# FlexiGlow_Rev_A.net
KiCad netlist of a schematic drawn in Altium Designer
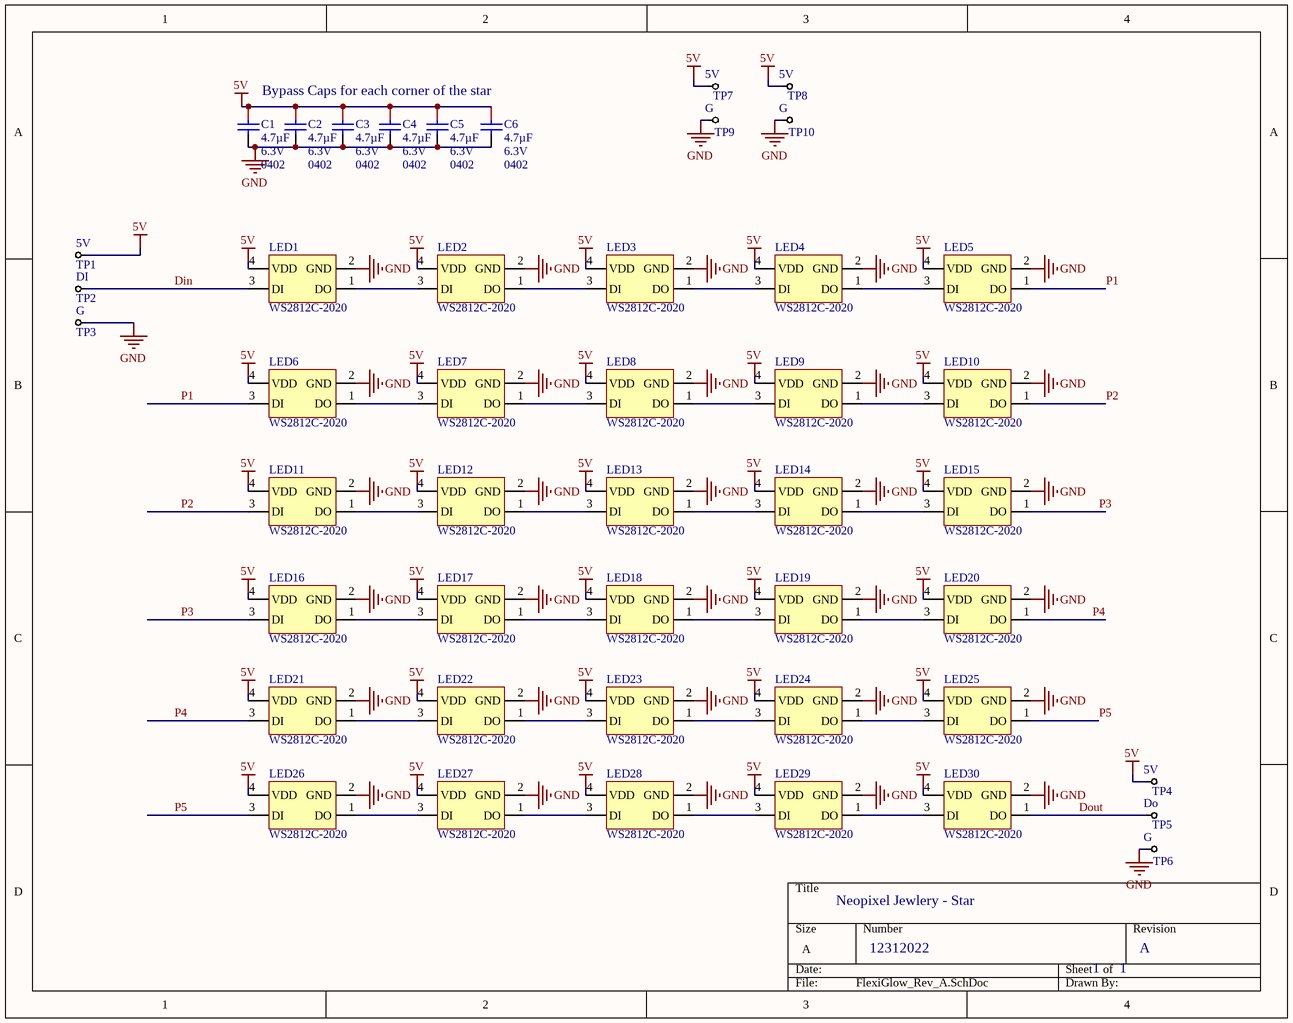
[diagram p0: FlexiGlow_Rev_A.SchDoc]

(export (version "E")
  (design (tool "Eeschema 10.0.6"))
  (components
    (comp (ref "C1")
      (value "4.7uF")
      (footprint "CAPC0402(1005)_N")
      (description "4.7uF 0402")
      (fields
        (field (name "MANUFACTURER") "Murata Electronics North America")
        (field (name "MANUFACTURER PART NUMBER") "GRM155R60J475ME47D")
        (field (name "CAPACITANCE") "4.7µF")
        (field (name "VOLTAGE - RATED") "6.3V")
        (field (name "PACKAGE / CASE") "0402")
      )
      (libsource (lib "Kyle-Passive") (part "CAP CER 4.7UF 6.3V 10% X5R 0402"))
    )
    (comp (ref "C2")
      (value "4.7uF")
      (footprint "CAPC0402(1005)_N")
      (description "4.7uF 0402")
      (fields
        (field (name "MANUFACTURER") "Murata Electronics North America")
        (field (name "MANUFACTURER PART NUMBER") "GRM155R60J475ME47D")
        (field (name "CAPACITANCE") "4.7µF")
        (field (name "VOLTAGE - RATED") "6.3V")
        (field (name "PACKAGE / CASE") "0402")
      )
      (libsource (lib "Kyle-Passive") (part "CAP CER 4.7UF 6.3V 10% X5R 0402"))
    )
    (comp (ref "C3")
      (value "4.7uF")
      (footprint "CAPC0402(1005)_N")
      (description "4.7uF 0402")
      (fields
        (field (name "MANUFACTURER") "Murata Electronics North America")
        (field (name "MANUFACTURER PART NUMBER") "GRM155R60J475ME47D")
        (field (name "CAPACITANCE") "4.7µF")
        (field (name "VOLTAGE - RATED") "6.3V")
        (field (name "PACKAGE / CASE") "0402")
      )
      (libsource (lib "Kyle-Passive") (part "CAP CER 4.7UF 6.3V 10% X5R 0402"))
    )
    (comp (ref "C4")
      (value "4.7uF")
      (footprint "CAPC0402(1005)_N")
      (description "4.7uF 0402")
      (fields
        (field (name "MANUFACTURER") "Murata Electronics North America")
        (field (name "MANUFACTURER PART NUMBER") "GRM155R60J475ME47D")
        (field (name "CAPACITANCE") "4.7µF")
        (field (name "VOLTAGE - RATED") "6.3V")
        (field (name "PACKAGE / CASE") "0402")
      )
      (libsource (lib "Kyle-Passive") (part "CAP CER 4.7UF 6.3V 10% X5R 0402"))
    )
    (comp (ref "C5")
      (value "4.7uF")
      (footprint "CAPC0402(1005)_N")
      (description "4.7uF 0402")
      (fields
        (field (name "MANUFACTURER") "Murata Electronics North America")
        (field (name "MANUFACTURER PART NUMBER") "GRM155R60J475ME47D")
        (field (name "CAPACITANCE") "4.7µF")
        (field (name "VOLTAGE - RATED") "6.3V")
        (field (name "PACKAGE / CASE") "0402")
      )
      (libsource (lib "Kyle-Passive") (part "CAP CER 4.7UF 6.3V 10% X5R 0402"))
    )
    (comp (ref "C6")
      (value "4.7uF")
      (footprint "CAPC0402(1005)_N")
      (description "4.7uF 0402")
      (fields
        (field (name "MANUFACTURER") "Murata Electronics North America")
        (field (name "MANUFACTURER PART NUMBER") "GRM155R60J475ME47D")
        (field (name "CAPACITANCE") "4.7µF")
        (field (name "VOLTAGE - RATED") "6.3V")
        (field (name "PACKAGE / CASE") "0402")
      )
      (libsource (lib "Kyle-Passive") (part "CAP CER 4.7UF 6.3V 10% X5R 0402"))
    )
    (comp (ref "LED1")
      (value "WS2812C-2020")
      (footprint "WS2812C-2020")
      (description "Neopixel")
      (libsource (lib "Kyle-Diode-Opto-LED") (part "WS2812C-2020"))
    )
    (comp (ref "LED2")
      (value "WS2812C-2020")
      (footprint "WS2812C-2020")
      (description "Neopixel")
      (libsource (lib "Kyle-Diode-Opto-LED") (part "WS2812C-2020"))
    )
    (comp (ref "LED3")
      (value "WS2812C-2020")
      (footprint "WS2812C-2020")
      (description "Neopixel")
      (libsource (lib "Kyle-Diode-Opto-LED") (part "WS2812C-2020"))
    )
    (comp (ref "LED4")
      (value "WS2812C-2020")
      (footprint "WS2812C-2020")
      (description "Neopixel")
      (libsource (lib "Kyle-Diode-Opto-LED") (part "WS2812C-2020"))
    )
    (comp (ref "LED5")
      (value "WS2812C-2020")
      (footprint "WS2812C-2020")
      (description "Neopixel")
      (libsource (lib "Kyle-Diode-Opto-LED") (part "WS2812C-2020"))
    )
    (comp (ref "LED6")
      (value "WS2812C-2020")
      (footprint "WS2812C-2020")
      (description "Neopixel")
      (libsource (lib "Kyle-Diode-Opto-LED") (part "WS2812C-2020"))
    )
    (comp (ref "LED7")
      (value "WS2812C-2020")
      (footprint "WS2812C-2020")
      (description "Neopixel")
      (libsource (lib "Kyle-Diode-Opto-LED") (part "WS2812C-2020"))
    )
    (comp (ref "LED8")
      (value "WS2812C-2020")
      (footprint "WS2812C-2020")
      (description "Neopixel")
      (libsource (lib "Kyle-Diode-Opto-LED") (part "WS2812C-2020"))
    )
    (comp (ref "LED9")
      (value "WS2812C-2020")
      (footprint "WS2812C-2020")
      (description "Neopixel")
      (libsource (lib "Kyle-Diode-Opto-LED") (part "WS2812C-2020"))
    )
    (comp (ref "LED10")
      (value "WS2812C-2020")
      (footprint "WS2812C-2020")
      (description "Neopixel")
      (libsource (lib "Kyle-Diode-Opto-LED") (part "WS2812C-2020"))
    )
    (comp (ref "LED11")
      (value "WS2812C-2020")
      (footprint "WS2812C-2020")
      (description "Neopixel")
      (libsource (lib "Kyle-Diode-Opto-LED") (part "WS2812C-2020"))
    )
    (comp (ref "LED12")
      (value "WS2812C-2020")
      (footprint "WS2812C-2020")
      (description "Neopixel")
      (libsource (lib "Kyle-Diode-Opto-LED") (part "WS2812C-2020"))
    )
    (comp (ref "LED13")
      (value "WS2812C-2020")
      (footprint "WS2812C-2020")
      (description "Neopixel")
      (libsource (lib "Kyle-Diode-Opto-LED") (part "WS2812C-2020"))
    )
    (comp (ref "LED14")
      (value "WS2812C-2020")
      (footprint "WS2812C-2020")
      (description "Neopixel")
      (libsource (lib "Kyle-Diode-Opto-LED") (part "WS2812C-2020"))
    )
    (comp (ref "LED15")
      (value "WS2812C-2020")
      (footprint "WS2812C-2020")
      (description "Neopixel")
      (libsource (lib "Kyle-Diode-Opto-LED") (part "WS2812C-2020"))
    )
    (comp (ref "LED16")
      (value "WS2812C-2020")
      (footprint "WS2812C-2020")
      (description "Neopixel")
      (libsource (lib "Kyle-Diode-Opto-LED") (part "WS2812C-2020"))
    )
    (comp (ref "LED17")
      (value "WS2812C-2020")
      (footprint "WS2812C-2020")
      (description "Neopixel")
      (libsource (lib "Kyle-Diode-Opto-LED") (part "WS2812C-2020"))
    )
    (comp (ref "LED18")
      (value "WS2812C-2020")
      (footprint "WS2812C-2020")
      (description "Neopixel")
      (libsource (lib "Kyle-Diode-Opto-LED") (part "WS2812C-2020"))
    )
    (comp (ref "LED19")
      (value "WS2812C-2020")
      (footprint "WS2812C-2020")
      (description "Neopixel")
      (libsource (lib "Kyle-Diode-Opto-LED") (part "WS2812C-2020"))
    )
    (comp (ref "LED20")
      (value "WS2812C-2020")
      (footprint "WS2812C-2020")
      (description "Neopixel")
      (libsource (lib "Kyle-Diode-Opto-LED") (part "WS2812C-2020"))
    )
    (comp (ref "LED21")
      (value "WS2812C-2020")
      (footprint "WS2812C-2020")
      (description "Neopixel")
      (libsource (lib "Kyle-Diode-Opto-LED") (part "WS2812C-2020"))
    )
    (comp (ref "LED22")
      (value "WS2812C-2020")
      (footprint "WS2812C-2020")
      (description "Neopixel")
      (libsource (lib "Kyle-Diode-Opto-LED") (part "WS2812C-2020"))
    )
    (comp (ref "LED23")
      (value "WS2812C-2020")
      (footprint "WS2812C-2020")
      (description "Neopixel")
      (libsource (lib "Kyle-Diode-Opto-LED") (part "WS2812C-2020"))
    )
    (comp (ref "LED24")
      (value "WS2812C-2020")
      (footprint "WS2812C-2020")
      (description "Neopixel")
      (libsource (lib "Kyle-Diode-Opto-LED") (part "WS2812C-2020"))
    )
    (comp (ref "LED25")
      (value "WS2812C-2020")
      (footprint "WS2812C-2020")
      (description "Neopixel")
      (libsource (lib "Kyle-Diode-Opto-LED") (part "WS2812C-2020"))
    )
    (comp (ref "LED26")
      (value "WS2812C-2020")
      (footprint "WS2812C-2020")
      (description "Neopixel")
      (libsource (lib "Kyle-Diode-Opto-LED") (part "WS2812C-2020"))
    )
    (comp (ref "LED27")
      (value "WS2812C-2020")
      (footprint "WS2812C-2020")
      (description "Neopixel")
      (libsource (lib "Kyle-Diode-Opto-LED") (part "WS2812C-2020"))
    )
    (comp (ref "LED28")
      (value "WS2812C-2020")
      (footprint "WS2812C-2020")
      (description "Neopixel")
      (libsource (lib "Kyle-Diode-Opto-LED") (part "WS2812C-2020"))
    )
    (comp (ref "LED29")
      (value "WS2812C-2020")
      (footprint "WS2812C-2020")
      (description "Neopixel")
      (libsource (lib "Kyle-Diode-Opto-LED") (part "WS2812C-2020"))
    )
    (comp (ref "LED30")
      (value "WS2812C-2020")
      (footprint "WS2812C-2020")
      (description "Neopixel")
      (libsource (lib "Kyle-Diode-Opto-LED") (part "WS2812C-2020"))
    )
    (comp (ref "TP1")
      (value "5V")
      (footprint "TestPoint-Micro")
      (description "Test Point")
      (libsource (lib "Kyle-Misc") (part "TestPoint, small"))
    )
    (comp (ref "TP2")
      (value "DI")
      (footprint "TestPoint-Micro")
      (description "Test Point")
      (libsource (lib "Kyle-Misc") (part "TestPoint, small"))
    )
    (comp (ref "TP3")
      (value "G")
      (footprint "TestPoint-Micro")
      (description "Test Point")
      (libsource (lib "Kyle-Misc") (part "TestPoint, small"))
    )
    (comp (ref "TP4")
      (value "5V")
      (footprint "TestPoint-Micro")
      (description "Test Point")
      (libsource (lib "Kyle-Misc") (part "TestPoint, small"))
    )
    (comp (ref "TP5")
      (value "Do")
      (footprint "TestPoint-Micro")
      (description "Test Point")
      (libsource (lib "Kyle-Misc") (part "TestPoint, small"))
    )
    (comp (ref "TP6")
      (value "G")
      (footprint "TestPoint-Micro")
      (description "Test Point")
      (libsource (lib "Kyle-Misc") (part "TestPoint, small"))
    )
    (comp (ref "TP7")
      (value "5V")
      (footprint "TestPoint-Micro")
      (description "Test Point")
      (libsource (lib "Kyle-Misc") (part "TestPoint, small"))
    )
    (comp (ref "TP8")
      (value "5V")
      (footprint "TestPoint-Micro")
      (description "Test Point")
      (libsource (lib "Kyle-Misc") (part "TestPoint, small"))
    )
    (comp (ref "TP9")
      (value "G")
      (footprint "TestPoint-Micro")
      (description "Test Point")
      (libsource (lib "Kyle-Misc") (part "TestPoint, small"))
    )
    (comp (ref "TP10")
      (value "G")
      (footprint "TestPoint-Micro")
      (description "Test Point")
      (libsource (lib "Kyle-Misc") (part "TestPoint, small"))
    )
  )
  (nets
    (net (code "1") (name "/Din") (class "Default")
      (node (ref "LED1") (pin "3") (pinfunction "DI_3") (pintype "power_in"))
      (node (ref "TP2") (pin "1") (pinfunction "1_1") (pintype "passive"))
    )
    (net (code "2") (name "/Dout") (class "Default")
      (node (ref "LED30") (pin "1") (pinfunction "DO_1") (pintype "power_in"))
      (node (ref "TP5") (pin "1") (pinfunction "1_1") (pintype "passive"))
    )
    (net (code "3") (name "/P1") (class "Default")
      (node (ref "LED5") (pin "1") (pinfunction "DO_1") (pintype "power_in"))
      (node (ref "LED6") (pin "3") (pinfunction "DI_3") (pintype "power_in"))
    )
    (net (code "4") (name "/P2") (class "Default")
      (node (ref "LED10") (pin "1") (pinfunction "DO_1") (pintype "power_in"))
      (node (ref "LED11") (pin "3") (pinfunction "DI_3") (pintype "power_in"))
    )
    (net (code "5") (name "/P3") (class "Default")
      (node (ref "LED15") (pin "1") (pinfunction "DO_1") (pintype "power_in"))
      (node (ref "LED16") (pin "3") (pinfunction "DI_3") (pintype "power_in"))
    )
    (net (code "6") (name "/P4") (class "Default")
      (node (ref "LED20") (pin "1") (pinfunction "DO_1") (pintype "power_in"))
      (node (ref "LED21") (pin "3") (pinfunction "DI_3") (pintype "power_in"))
    )
    (net (code "7") (name "/P5") (class "Default")
      (node (ref "LED25") (pin "1") (pinfunction "DO_1") (pintype "power_in"))
      (node (ref "LED26") (pin "3") (pinfunction "DI_3") (pintype "power_in"))
    )
    (net (code "8") (name "5V") (class "Default")
      (node (ref "C1") (pin "1") (pinfunction "1_1") (pintype "passive"))
      (node (ref "C2") (pin "1") (pinfunction "1_1") (pintype "passive"))
      (node (ref "C3") (pin "1") (pinfunction "1_1") (pintype "passive"))
      (node (ref "C4") (pin "1") (pinfunction "1_1") (pintype "passive"))
      (node (ref "C5") (pin "1") (pinfunction "1_1") (pintype "passive"))
      (node (ref "C6") (pin "1") (pinfunction "1_1") (pintype "passive"))
      (node (ref "LED1") (pin "4") (pinfunction "VDD_4") (pintype "power_in"))
      (node (ref "LED10") (pin "4") (pinfunction "VDD_4") (pintype "power_in"))
      (node (ref "LED11") (pin "4") (pinfunction "VDD_4") (pintype "power_in"))
      (node (ref "LED12") (pin "4") (pinfunction "VDD_4") (pintype "power_in"))
      (node (ref "LED13") (pin "4") (pinfunction "VDD_4") (pintype "power_in"))
      (node (ref "LED14") (pin "4") (pinfunction "VDD_4") (pintype "power_in"))
      (node (ref "LED15") (pin "4") (pinfunction "VDD_4") (pintype "power_in"))
      (node (ref "LED16") (pin "4") (pinfunction "VDD_4") (pintype "power_in"))
      (node (ref "LED17") (pin "4") (pinfunction "VDD_4") (pintype "power_in"))
      (node (ref "LED18") (pin "4") (pinfunction "VDD_4") (pintype "power_in"))
      (node (ref "LED19") (pin "4") (pinfunction "VDD_4") (pintype "power_in"))
      (node (ref "LED2") (pin "4") (pinfunction "VDD_4") (pintype "power_in"))
      (node (ref "LED20") (pin "4") (pinfunction "VDD_4") (pintype "power_in"))
      (node (ref "LED21") (pin "4") (pinfunction "VDD_4") (pintype "power_in"))
      (node (ref "LED22") (pin "4") (pinfunction "VDD_4") (pintype "power_in"))
      (node (ref "LED23") (pin "4") (pinfunction "VDD_4") (pintype "power_in"))
      (node (ref "LED24") (pin "4") (pinfunction "VDD_4") (pintype "power_in"))
      (node (ref "LED25") (pin "4") (pinfunction "VDD_4") (pintype "power_in"))
      (node (ref "LED26") (pin "4") (pinfunction "VDD_4") (pintype "power_in"))
      (node (ref "LED27") (pin "4") (pinfunction "VDD_4") (pintype "power_in"))
      (node (ref "LED28") (pin "4") (pinfunction "VDD_4") (pintype "power_in"))
      (node (ref "LED29") (pin "4") (pinfunction "VDD_4") (pintype "power_in"))
      (node (ref "LED3") (pin "4") (pinfunction "VDD_4") (pintype "power_in"))
      (node (ref "LED30") (pin "4") (pinfunction "VDD_4") (pintype "power_in"))
      (node (ref "LED4") (pin "4") (pinfunction "VDD_4") (pintype "power_in"))
      (node (ref "LED5") (pin "4") (pinfunction "VDD_4") (pintype "power_in"))
      (node (ref "LED6") (pin "4") (pinfunction "VDD_4") (pintype "power_in"))
      (node (ref "LED7") (pin "4") (pinfunction "VDD_4") (pintype "power_in"))
      (node (ref "LED8") (pin "4") (pinfunction "VDD_4") (pintype "power_in"))
      (node (ref "LED9") (pin "4") (pinfunction "VDD_4") (pintype "power_in"))
      (node (ref "TP1") (pin "1") (pinfunction "1_1") (pintype "passive"))
      (node (ref "TP4") (pin "1") (pinfunction "1_1") (pintype "passive"))
      (node (ref "TP7") (pin "1") (pinfunction "1_1") (pintype "passive"))
      (node (ref "TP8") (pin "1") (pinfunction "1_1") (pintype "passive"))
    )
    (net (code "9") (name "GND") (class "Default")
      (node (ref "C1") (pin "2") (pinfunction "2_2") (pintype "passive"))
      (node (ref "C2") (pin "2") (pinfunction "2_2") (pintype "passive"))
      (node (ref "C3") (pin "2") (pinfunction "2_2") (pintype "passive"))
      (node (ref "C4") (pin "2") (pinfunction "2_2") (pintype "passive"))
      (node (ref "C5") (pin "2") (pinfunction "2_2") (pintype "passive"))
      (node (ref "C6") (pin "2") (pinfunction "2_2") (pintype "passive"))
      (node (ref "LED1") (pin "2") (pinfunction "GND_2") (pintype "power_in"))
      (node (ref "LED10") (pin "2") (pinfunction "GND_2") (pintype "power_in"))
      (node (ref "LED11") (pin "2") (pinfunction "GND_2") (pintype "power_in"))
      (node (ref "LED12") (pin "2") (pinfunction "GND_2") (pintype "power_in"))
      (node (ref "LED13") (pin "2") (pinfunction "GND_2") (pintype "power_in"))
      (node (ref "LED14") (pin "2") (pinfunction "GND_2") (pintype "power_in"))
      (node (ref "LED15") (pin "2") (pinfunction "GND_2") (pintype "power_in"))
      (node (ref "LED16") (pin "2") (pinfunction "GND_2") (pintype "power_in"))
      (node (ref "LED17") (pin "2") (pinfunction "GND_2") (pintype "power_in"))
      (node (ref "LED18") (pin "2") (pinfunction "GND_2") (pintype "power_in"))
      (node (ref "LED19") (pin "2") (pinfunction "GND_2") (pintype "power_in"))
      (node (ref "LED2") (pin "2") (pinfunction "GND_2") (pintype "power_in"))
      (node (ref "LED20") (pin "2") (pinfunction "GND_2") (pintype "power_in"))
      (node (ref "LED21") (pin "2") (pinfunction "GND_2") (pintype "power_in"))
      (node (ref "LED22") (pin "2") (pinfunction "GND_2") (pintype "power_in"))
      (node (ref "LED23") (pin "2") (pinfunction "GND_2") (pintype "power_in"))
      (node (ref "LED24") (pin "2") (pinfunction "GND_2") (pintype "power_in"))
      (node (ref "LED25") (pin "2") (pinfunction "GND_2") (pintype "power_in"))
      (node (ref "LED26") (pin "2") (pinfunction "GND_2") (pintype "power_in"))
      (node (ref "LED27") (pin "2") (pinfunction "GND_2") (pintype "power_in"))
      (node (ref "LED28") (pin "2") (pinfunction "GND_2") (pintype "power_in"))
      (node (ref "LED29") (pin "2") (pinfunction "GND_2") (pintype "power_in"))
      (node (ref "LED3") (pin "2") (pinfunction "GND_2") (pintype "power_in"))
      (node (ref "LED30") (pin "2") (pinfunction "GND_2") (pintype "power_in"))
      (node (ref "LED4") (pin "2") (pinfunction "GND_2") (pintype "power_in"))
      (node (ref "LED5") (pin "2") (pinfunction "GND_2") (pintype "power_in"))
      (node (ref "LED6") (pin "2") (pinfunction "GND_2") (pintype "power_in"))
      (node (ref "LED7") (pin "2") (pinfunction "GND_2") (pintype "power_in"))
      (node (ref "LED8") (pin "2") (pinfunction "GND_2") (pintype "power_in"))
      (node (ref "LED9") (pin "2") (pinfunction "GND_2") (pintype "power_in"))
      (node (ref "TP10") (pin "1") (pinfunction "1_1") (pintype "passive"))
      (node (ref "TP3") (pin "1") (pinfunction "1_1") (pintype "passive"))
      (node (ref "TP6") (pin "1") (pinfunction "1_1") (pintype "passive"))
      (node (ref "TP9") (pin "1") (pinfunction "1_1") (pintype "passive"))
    )
    (net (code "10") (name "Net-(LED1-DO)") (class "Default")
      (node (ref "LED1") (pin "1") (pinfunction "DO_1") (pintype "power_in"))
      (node (ref "LED2") (pin "3") (pinfunction "DI_3") (pintype "power_in"))
    )
    (net (code "11") (name "Net-(LED2-DO)") (class "Default")
      (node (ref "LED2") (pin "1") (pinfunction "DO_1") (pintype "power_in"))
      (node (ref "LED3") (pin "3") (pinfunction "DI_3") (pintype "power_in"))
    )
    (net (code "12") (name "Net-(LED3-DO)") (class "Default")
      (node (ref "LED3") (pin "1") (pinfunction "DO_1") (pintype "power_in"))
      (node (ref "LED4") (pin "3") (pinfunction "DI_3") (pintype "power_in"))
    )
    (net (code "13") (name "Net-(LED4-DO)") (class "Default")
      (node (ref "LED4") (pin "1") (pinfunction "DO_1") (pintype "power_in"))
      (node (ref "LED5") (pin "3") (pinfunction "DI_3") (pintype "power_in"))
    )
    (net (code "14") (name "Net-(LED6-DO)") (class "Default")
      (node (ref "LED6") (pin "1") (pinfunction "DO_1") (pintype "power_in"))
      (node (ref "LED7") (pin "3") (pinfunction "DI_3") (pintype "power_in"))
    )
    (net (code "15") (name "Net-(LED7-DO)") (class "Default")
      (node (ref "LED7") (pin "1") (pinfunction "DO_1") (pintype "power_in"))
      (node (ref "LED8") (pin "3") (pinfunction "DI_3") (pintype "power_in"))
    )
    (net (code "16") (name "Net-(LED8-DO)") (class "Default")
      (node (ref "LED8") (pin "1") (pinfunction "DO_1") (pintype "power_in"))
      (node (ref "LED9") (pin "3") (pinfunction "DI_3") (pintype "power_in"))
    )
    (net (code "17") (name "Net-(LED10-DI)") (class "Default")
      (node (ref "LED10") (pin "3") (pinfunction "DI_3") (pintype "power_in"))
      (node (ref "LED9") (pin "1") (pinfunction "DO_1") (pintype "power_in"))
    )
    (net (code "18") (name "Net-(LED11-DO)") (class "Default")
      (node (ref "LED11") (pin "1") (pinfunction "DO_1") (pintype "power_in"))
      (node (ref "LED12") (pin "3") (pinfunction "DI_3") (pintype "power_in"))
    )
    (net (code "19") (name "Net-(LED12-DO)") (class "Default")
      (node (ref "LED12") (pin "1") (pinfunction "DO_1") (pintype "power_in"))
      (node (ref "LED13") (pin "3") (pinfunction "DI_3") (pintype "power_in"))
    )
    (net (code "20") (name "Net-(LED13-DO)") (class "Default")
      (node (ref "LED13") (pin "1") (pinfunction "DO_1") (pintype "power_in"))
      (node (ref "LED14") (pin "3") (pinfunction "DI_3") (pintype "power_in"))
    )
    (net (code "21") (name "Net-(LED14-DO)") (class "Default")
      (node (ref "LED14") (pin "1") (pinfunction "DO_1") (pintype "power_in"))
      (node (ref "LED15") (pin "3") (pinfunction "DI_3") (pintype "power_in"))
    )
    (net (code "22") (name "Net-(LED16-DO)") (class "Default")
      (node (ref "LED16") (pin "1") (pinfunction "DO_1") (pintype "power_in"))
      (node (ref "LED17") (pin "3") (pinfunction "DI_3") (pintype "power_in"))
    )
    (net (code "23") (name "Net-(LED17-DO)") (class "Default")
      (node (ref "LED17") (pin "1") (pinfunction "DO_1") (pintype "power_in"))
      (node (ref "LED18") (pin "3") (pinfunction "DI_3") (pintype "power_in"))
    )
    (net (code "24") (name "Net-(LED18-DO)") (class "Default")
      (node (ref "LED18") (pin "1") (pinfunction "DO_1") (pintype "power_in"))
      (node (ref "LED19") (pin "3") (pinfunction "DI_3") (pintype "power_in"))
    )
    (net (code "25") (name "Net-(LED19-DO)") (class "Default")
      (node (ref "LED19") (pin "1") (pinfunction "DO_1") (pintype "power_in"))
      (node (ref "LED20") (pin "3") (pinfunction "DI_3") (pintype "power_in"))
    )
    (net (code "26") (name "Net-(LED21-DO)") (class "Default")
      (node (ref "LED21") (pin "1") (pinfunction "DO_1") (pintype "power_in"))
      (node (ref "LED22") (pin "3") (pinfunction "DI_3") (pintype "power_in"))
    )
    (net (code "27") (name "Net-(LED22-DO)") (class "Default")
      (node (ref "LED22") (pin "1") (pinfunction "DO_1") (pintype "power_in"))
      (node (ref "LED23") (pin "3") (pinfunction "DI_3") (pintype "power_in"))
    )
    (net (code "28") (name "Net-(LED23-DO)") (class "Default")
      (node (ref "LED23") (pin "1") (pinfunction "DO_1") (pintype "power_in"))
      (node (ref "LED24") (pin "3") (pinfunction "DI_3") (pintype "power_in"))
    )
    (net (code "29") (name "Net-(LED24-DO)") (class "Default")
      (node (ref "LED24") (pin "1") (pinfunction "DO_1") (pintype "power_in"))
      (node (ref "LED25") (pin "3") (pinfunction "DI_3") (pintype "power_in"))
    )
    (net (code "30") (name "Net-(LED26-DO)") (class "Default")
      (node (ref "LED26") (pin "1") (pinfunction "DO_1") (pintype "power_in"))
      (node (ref "LED27") (pin "3") (pinfunction "DI_3") (pintype "power_in"))
    )
    (net (code "31") (name "Net-(LED27-DO)") (class "Default")
      (node (ref "LED27") (pin "1") (pinfunction "DO_1") (pintype "power_in"))
      (node (ref "LED28") (pin "3") (pinfunction "DI_3") (pintype "power_in"))
    )
    (net (code "32") (name "Net-(LED28-DO)") (class "Default")
      (node (ref "LED28") (pin "1") (pinfunction "DO_1") (pintype "power_in"))
      (node (ref "LED29") (pin "3") (pinfunction "DI_3") (pintype "power_in"))
    )
    (net (code "33") (name "Net-(LED29-DO)") (class "Default")
      (node (ref "LED29") (pin "1") (pinfunction "DO_1") (pintype "power_in"))
      (node (ref "LED30") (pin "3") (pinfunction "DI_3") (pintype "power_in"))
    )
  )
)
